# Tractive_System_Active_Light_rev2.net
KiCad netlist of a schematic drawn in EAGLE
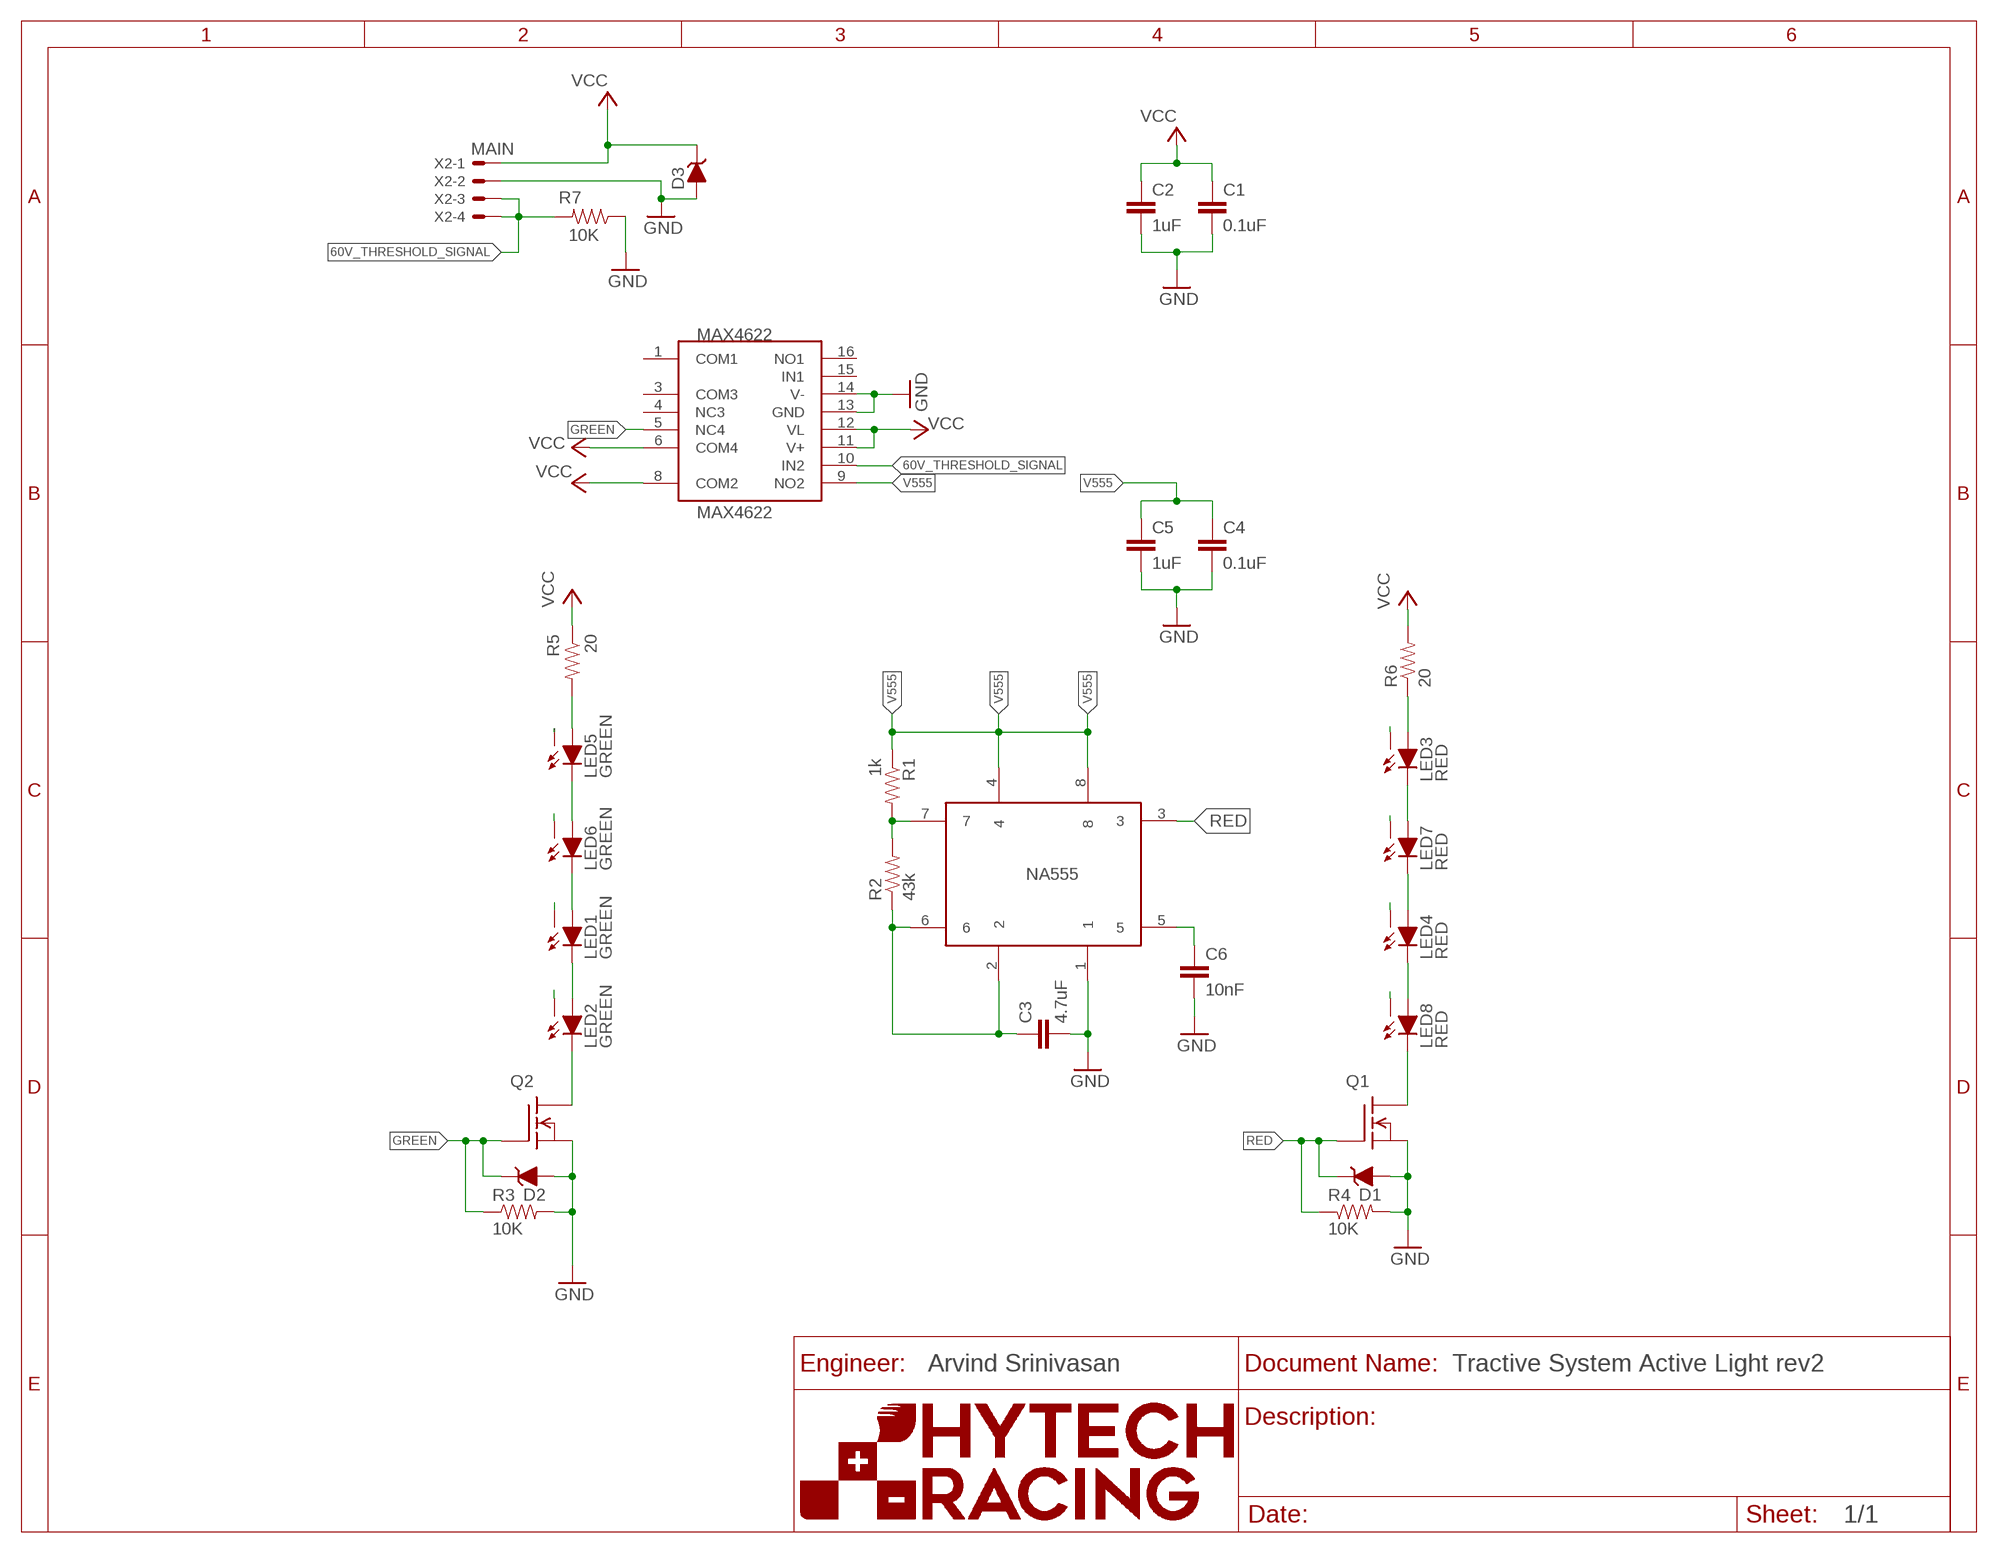
[diagram p0: schematic, sheet 1]

(export (version "E")
  (design (tool "Eeschema 10.0.6"))
  (components
    (comp (ref "C1")
      (value "0.1uF")
      (footprint "eagle-import:0603-CAP")
      (fields (field (name "TOLERANCE") "5%") (field (name "VOLTAGE") "25V"))
      (libsource (lib "eagle-import") (part "CAP0603-CAP"))
    )
    (comp (ref "C2")
      (value "1uF")
      (footprint "eagle-import:0603-CAP")
      (fields (field (name "TOLERANCE") "5%") (field (name "VOLTAGE") "25V"))
      (libsource (lib "eagle-import") (part "CAP0603-CAP"))
    )
    (comp (ref "C3")
      (value "4.7uF")
      (footprint "eagle-import:0603-CAP")
      (fields (field (name "TOLERANCE") "5%") (field (name "VOLTAGE") "25V"))
      (libsource (lib "eagle-import") (part "CAP0603-CAP"))
    )
    (comp (ref "C4")
      (value "0.1uF")
      (footprint "eagle-import:0603-CAP")
      (fields (field (name "TOLERANCE") "5%") (field (name "VOLTAGE") "25V"))
      (libsource (lib "eagle-import") (part "CAP0603-CAP"))
    )
    (comp (ref "C5")
      (value "1uF")
      (footprint "eagle-import:0603-CAP")
      (fields (field (name "TOLERANCE") "5%") (field (name "VOLTAGE") "25V"))
      (libsource (lib "eagle-import") (part "CAP0603-CAP"))
    )
    (comp (ref "C6")
      (value "10nF")
      (footprint "eagle-import:0603-CAP")
      (fields (field (name "TOLERANCE") "5%") (field (name "VOLTAGE") "25V"))
      (libsource (lib "eagle-import") (part "CAP0603-CAP"))
    )
    (comp (ref "D1")
      (value "MMBZ5246BLT1G")
      (footprint "eagle-import:SOT23")
      (libsource (lib "eagle-import") (part "DIODE_ZENER"))
    )
    (comp (ref "D2")
      (value "MMBZ5246BLT1G")
      (footprint "eagle-import:SOT23")
      (libsource (lib "eagle-import") (part "DIODE_ZENER"))
    )
    (comp (ref "D3")
      (value "D15V0S1U2LP1608")
      (footprint "eagle-import:0603_D")
      (libsource (lib "eagle-import") (part "DIODE_ZENER0603"))
    )
    (comp (ref "LED1")
      (value "GREEN")
      (footprint "eagle-import:XP-E2")
      (libsource (lib "eagle-import") (part "XP-E2XP-E2"))
    )
    (comp (ref "LED2")
      (value "GREEN")
      (footprint "eagle-import:XP-E2")
      (libsource (lib "eagle-import") (part "XP-E2XP-E2"))
    )
    (comp (ref "LED3")
      (value "RED")
      (footprint "eagle-import:XP-E2")
      (libsource (lib "eagle-import") (part "XP-E2XP-E2"))
    )
    (comp (ref "LED4")
      (value "RED")
      (footprint "eagle-import:XP-E2")
      (libsource (lib "eagle-import") (part "XP-E2XP-E2"))
    )
    (comp (ref "LED5")
      (value "GREEN")
      (footprint "eagle-import:XP-E2")
      (libsource (lib "eagle-import") (part "XP-E2XP-E2"))
    )
    (comp (ref "LED6")
      (value "GREEN")
      (footprint "eagle-import:XP-E2")
      (libsource (lib "eagle-import") (part "XP-E2XP-E2"))
    )
    (comp (ref "LED7")
      (value "RED")
      (footprint "eagle-import:XP-E2")
      (libsource (lib "eagle-import") (part "XP-E2XP-E2"))
    )
    (comp (ref "LED8")
      (value "RED")
      (footprint "eagle-import:XP-E2")
      (libsource (lib "eagle-import") (part "XP-E2XP-E2"))
    )
    (comp (ref "MAX4622")
      (value "MAX4622")
      (footprint "eagle-import:SO16")
      (libsource (lib "eagle-import") (part "MAX4622"))
    )
    (comp (ref "NA555")
      (value "NA555SO-8")
      (footprint "eagle-import:SOIC-08")
      (libsource (lib "eagle-import") (part "NA555SO-8"))
    )
    (comp (ref "Q1")
      (value "DMG3406LSOT")
      (footprint "eagle-import:SOT23")
      (libsource (lib "eagle-import") (part "DMG3406LSOT"))
    )
    (comp (ref "Q2")
      (value "DMG3406LSOT")
      (footprint "eagle-import:SOT23")
      (libsource (lib "eagle-import") (part "DMG3406LSOT"))
    )
    (comp (ref "R1")
      (value "1k")
      (footprint "eagle-import:0603-RES")
      (fields (field (name "TOLERANCE") "1%"))
      (libsource (lib "eagle-import") (part "RESISTOR0603-RES"))
    )
    (comp (ref "R2")
      (value "43k")
      (footprint "eagle-import:0603-RES")
      (fields (field (name "TOLERANCE") "1%"))
      (libsource (lib "eagle-import") (part "RESISTOR0603-RES"))
    )
    (comp (ref "R3")
      (value "10K")
      (footprint "eagle-import:0603-RES")
      (fields (field (name "TOLERANCE") "1%"))
      (libsource (lib "eagle-import") (part "RESISTOR0603-RES"))
    )
    (comp (ref "R4")
      (value "10K")
      (footprint "eagle-import:0603-RES")
      (fields (field (name "TOLERANCE") "1%"))
      (libsource (lib "eagle-import") (part "RESISTOR0603-RES"))
    )
    (comp (ref "R5")
      (value "20")
      (footprint "eagle-import:0603-RES")
      (fields (field (name "TOLERANCE") "1%"))
      (libsource (lib "eagle-import") (part "RESISTOR0603-RES"))
    )
    (comp (ref "R6")
      (value "20")
      (footprint "eagle-import:0603-RES")
      (fields (field (name "TOLERANCE") "1%"))
      (libsource (lib "eagle-import") (part "RESISTOR0603-RES"))
    )
    (comp (ref "R7")
      (value "10K")
      (footprint "eagle-import:0603-RES")
      (fields (field (name "TOLERANCE") "1%"))
      (libsource (lib "eagle-import") (part "RESISTOR0603-RES"))
    )
    (comp (ref "X2")
      (value "MAIN")
      (footprint "eagle-import:NANO-FIT_RIGHT_ANGLE-4-SURFACE")
      (libsource (lib "eagle-import") (part "CONNECTOR-4NANO-FIT_RIGHT_ANGLE-4-SURFACE"))
    )
  )
  (nets
    (net (code "1") (name "/THERM") (class "Default")
      (node (ref "LED1") (pin "X") (pinfunction "X_X") (pintype "passive"))
      (node (ref "LED2") (pin "X") (pinfunction "X_X") (pintype "passive"))
      (node (ref "LED3") (pin "X") (pinfunction "X_X") (pintype "passive"))
      (node (ref "LED4") (pin "X") (pinfunction "X_X") (pintype "passive"))
      (node (ref "LED5") (pin "X") (pinfunction "X_X") (pintype "passive"))
      (node (ref "LED6") (pin "X") (pinfunction "X_X") (pintype "passive"))
      (node (ref "LED7") (pin "X") (pinfunction "X_X") (pintype "passive"))
      (node (ref "LED8") (pin "X") (pinfunction "X_X") (pintype "passive"))
    )
    (net (code "2") (name "60V_THRESHOLD_SIGNAL") (class "Default")
      (node (ref "MAX4622") (pin "10") (pinfunction "IN2_10") (pintype "bidirectional"))
      (node (ref "R7") (pin "2") (pinfunction "2_2") (pintype "passive"))
      (node (ref "X2") (pin "3") (pinfunction "S_3") (pintype "passive"))
      (node (ref "X2") (pin "4") (pinfunction "S_4") (pintype "passive"))
    )
    (net (code "3") (name "GND") (class "Default")
      (node (ref "C1") (pin "2") (pinfunction "2_2") (pintype "passive"))
      (node (ref "C2") (pin "2") (pinfunction "2_2") (pintype "passive"))
      (node (ref "C3") (pin "2") (pinfunction "2_2") (pintype "passive"))
      (node (ref "C4") (pin "2") (pinfunction "2_2") (pintype "passive"))
      (node (ref "C5") (pin "2") (pinfunction "2_2") (pintype "passive"))
      (node (ref "C6") (pin "2") (pinfunction "2_2") (pintype "passive"))
      (node (ref "D1") (pin "1") (pinfunction "A_1") (pintype "passive"))
      (node (ref "D2") (pin "1") (pinfunction "A_1") (pintype "passive"))
      (node (ref "D3") (pin "A") (pinfunction "A_A") (pintype "passive"))
      (node (ref "MAX4622") (pin "13") (pinfunction "GND_13") (pintype "bidirectional"))
      (node (ref "MAX4622") (pin "14") (pinfunction "V-_14") (pintype "bidirectional"))
      (node (ref "NA555") (pin "1") (pinfunction "1_1") (pintype "bidirectional"))
      (node (ref "Q1") (pin "2") (pinfunction "S_2") (pintype "passive"))
      (node (ref "Q2") (pin "2") (pinfunction "S_2") (pintype "passive"))
      (node (ref "R3") (pin "2") (pinfunction "2_2") (pintype "passive"))
      (node (ref "R4") (pin "2") (pinfunction "2_2") (pintype "passive"))
      (node (ref "R7") (pin "1") (pinfunction "1_1") (pintype "passive"))
      (node (ref "X2") (pin "2") (pinfunction "S_2") (pintype "passive"))
    )
    (net (code "4") (name "GREEN") (class "Default")
      (node (ref "D2") (pin "3") (pinfunction "C_3") (pintype "passive"))
      (node (ref "MAX4622") (pin "5") (pinfunction "NC4_5") (pintype "bidirectional"))
      (node (ref "Q2") (pin "1") (pinfunction "G_1") (pintype "passive"))
      (node (ref "R3") (pin "1") (pinfunction "1_1") (pintype "passive"))
    )
    (net (code "5") (name "Net-(C3-Pad1)") (class "Default")
      (node (ref "C3") (pin "1") (pinfunction "1_1") (pintype "passive"))
      (node (ref "NA555") (pin "2") (pinfunction "2_2") (pintype "bidirectional"))
      (node (ref "NA555") (pin "6") (pinfunction "6_6") (pintype "bidirectional"))
      (node (ref "R2") (pin "1") (pinfunction "1_1") (pintype "passive"))
    )
    (net (code "6") (name "Net-(C6-Pad1)") (class "Default")
      (node (ref "C6") (pin "1") (pinfunction "1_1") (pintype "passive"))
      (node (ref "NA555") (pin "5") (pinfunction "5_5") (pintype "bidirectional"))
    )
    (net (code "7") (name "Net-(LED1-PadA)") (class "Default")
      (node (ref "LED1") (pin "A") (pinfunction "A_A") (pintype "passive"))
      (node (ref "LED6") (pin "C") (pinfunction "C_C") (pintype "passive"))
    )
    (net (code "8") (name "Net-(LED1-PadC)") (class "Default")
      (node (ref "LED1") (pin "C") (pinfunction "C_C") (pintype "passive"))
      (node (ref "LED2") (pin "A") (pinfunction "A_A") (pintype "passive"))
    )
    (net (code "9") (name "Net-(LED3-PadA)") (class "Default")
      (node (ref "LED3") (pin "A") (pinfunction "A_A") (pintype "passive"))
      (node (ref "R6") (pin "1") (pinfunction "1_1") (pintype "passive"))
    )
    (net (code "10") (name "Net-(LED3-PadC)") (class "Default")
      (node (ref "LED3") (pin "C") (pinfunction "C_C") (pintype "passive"))
      (node (ref "LED7") (pin "A") (pinfunction "A_A") (pintype "passive"))
    )
    (net (code "11") (name "Net-(LED4-PadA)") (class "Default")
      (node (ref "LED4") (pin "A") (pinfunction "A_A") (pintype "passive"))
      (node (ref "LED7") (pin "C") (pinfunction "C_C") (pintype "passive"))
    )
    (net (code "12") (name "Net-(LED4-PadC)") (class "Default")
      (node (ref "LED4") (pin "C") (pinfunction "C_C") (pintype "passive"))
      (node (ref "LED8") (pin "A") (pinfunction "A_A") (pintype "passive"))
    )
    (net (code "13") (name "Net-(LED5-PadA)") (class "Default")
      (node (ref "LED5") (pin "A") (pinfunction "A_A") (pintype "passive"))
      (node (ref "R5") (pin "2") (pinfunction "2_2") (pintype "passive"))
    )
    (net (code "14") (name "Net-(LED5-PadC)") (class "Default")
      (node (ref "LED5") (pin "C") (pinfunction "C_C") (pintype "passive"))
      (node (ref "LED6") (pin "A") (pinfunction "A_A") (pintype "passive"))
    )
    (net (code "15") (name "Net-(NA555-Pad7)") (class "Default")
      (node (ref "NA555") (pin "7") (pinfunction "7_7") (pintype "bidirectional"))
      (node (ref "R1") (pin "2") (pinfunction "2_2") (pintype "passive"))
      (node (ref "R2") (pin "2") (pinfunction "2_2") (pintype "passive"))
    )
    (net (code "16") (name "Net-(Q1-D)") (class "Default")
      (node (ref "LED8") (pin "C") (pinfunction "C_C") (pintype "passive"))
      (node (ref "Q1") (pin "3") (pinfunction "D_3") (pintype "passive"))
    )
    (net (code "17") (name "Net-(Q2-D)") (class "Default")
      (node (ref "LED2") (pin "C") (pinfunction "C_C") (pintype "passive"))
      (node (ref "Q2") (pin "3") (pinfunction "D_3") (pintype "passive"))
    )
    (net (code "18") (name "RED") (class "Default")
      (node (ref "D1") (pin "3") (pinfunction "C_3") (pintype "passive"))
      (node (ref "NA555") (pin "3") (pinfunction "3_3") (pintype "bidirectional"))
      (node (ref "Q1") (pin "1") (pinfunction "G_1") (pintype "passive"))
      (node (ref "R4") (pin "1") (pinfunction "1_1") (pintype "passive"))
    )
    (net (code "19") (name "V555") (class "Default")
      (node (ref "C4") (pin "1") (pinfunction "1_1") (pintype "passive"))
      (node (ref "C5") (pin "1") (pinfunction "1_1") (pintype "passive"))
      (node (ref "MAX4622") (pin "9") (pinfunction "NO2_9") (pintype "bidirectional"))
      (node (ref "NA555") (pin "4") (pinfunction "4_4") (pintype "bidirectional"))
      (node (ref "NA555") (pin "8") (pinfunction "8_8") (pintype "bidirectional"))
      (node (ref "R1") (pin "1") (pinfunction "1_1") (pintype "passive"))
    )
    (net (code "20") (name "VCC") (class "Default")
      (node (ref "C1") (pin "1") (pinfunction "1_1") (pintype "passive"))
      (node (ref "C2") (pin "1") (pinfunction "1_1") (pintype "passive"))
      (node (ref "D3") (pin "C") (pinfunction "C_C") (pintype "passive"))
      (node (ref "MAX4622") (pin "11") (pinfunction "V+_11") (pintype "bidirectional"))
      (node (ref "MAX4622") (pin "12") (pinfunction "VL_12") (pintype "bidirectional"))
      (node (ref "MAX4622") (pin "6") (pinfunction "COM4_6") (pintype "bidirectional"))
      (node (ref "MAX4622") (pin "8") (pinfunction "COM2_8") (pintype "bidirectional"))
      (node (ref "R5") (pin "1") (pinfunction "1_1") (pintype "passive"))
      (node (ref "R6") (pin "2") (pinfunction "2_2") (pintype "passive"))
      (node (ref "X2") (pin "1") (pinfunction "S_1") (pintype "passive"))
    )
    (net (code "21") (name "unconnected-(MAX4622-COM1-Pad1)") (class "Default")
      (node (ref "MAX4622") (pin "1") (pinfunction "COM1_1") (pintype "bidirectional"))
    )
    (net (code "22") (name "unconnected-(MAX4622-COM3-Pad3)") (class "Default")
      (node (ref "MAX4622") (pin "3") (pinfunction "COM3_3") (pintype "bidirectional"))
    )
    (net (code "23") (name "unconnected-(MAX4622-IN1-Pad15)") (class "Default")
      (node (ref "MAX4622") (pin "15") (pinfunction "IN1_15") (pintype "bidirectional"))
    )
    (net (code "24") (name "unconnected-(MAX4622-NC3-Pad4)") (class "Default")
      (node (ref "MAX4622") (pin "4") (pinfunction "NC3_4") (pintype "bidirectional"))
    )
    (net (code "25") (name "unconnected-(MAX4622-NO1-Pad16)") (class "Default")
      (node (ref "MAX4622") (pin "16") (pinfunction "NO1_16") (pintype "bidirectional"))
    )
  )
)
